# connector.net
KiCad netlist of a schematic drawn in Altium Designer
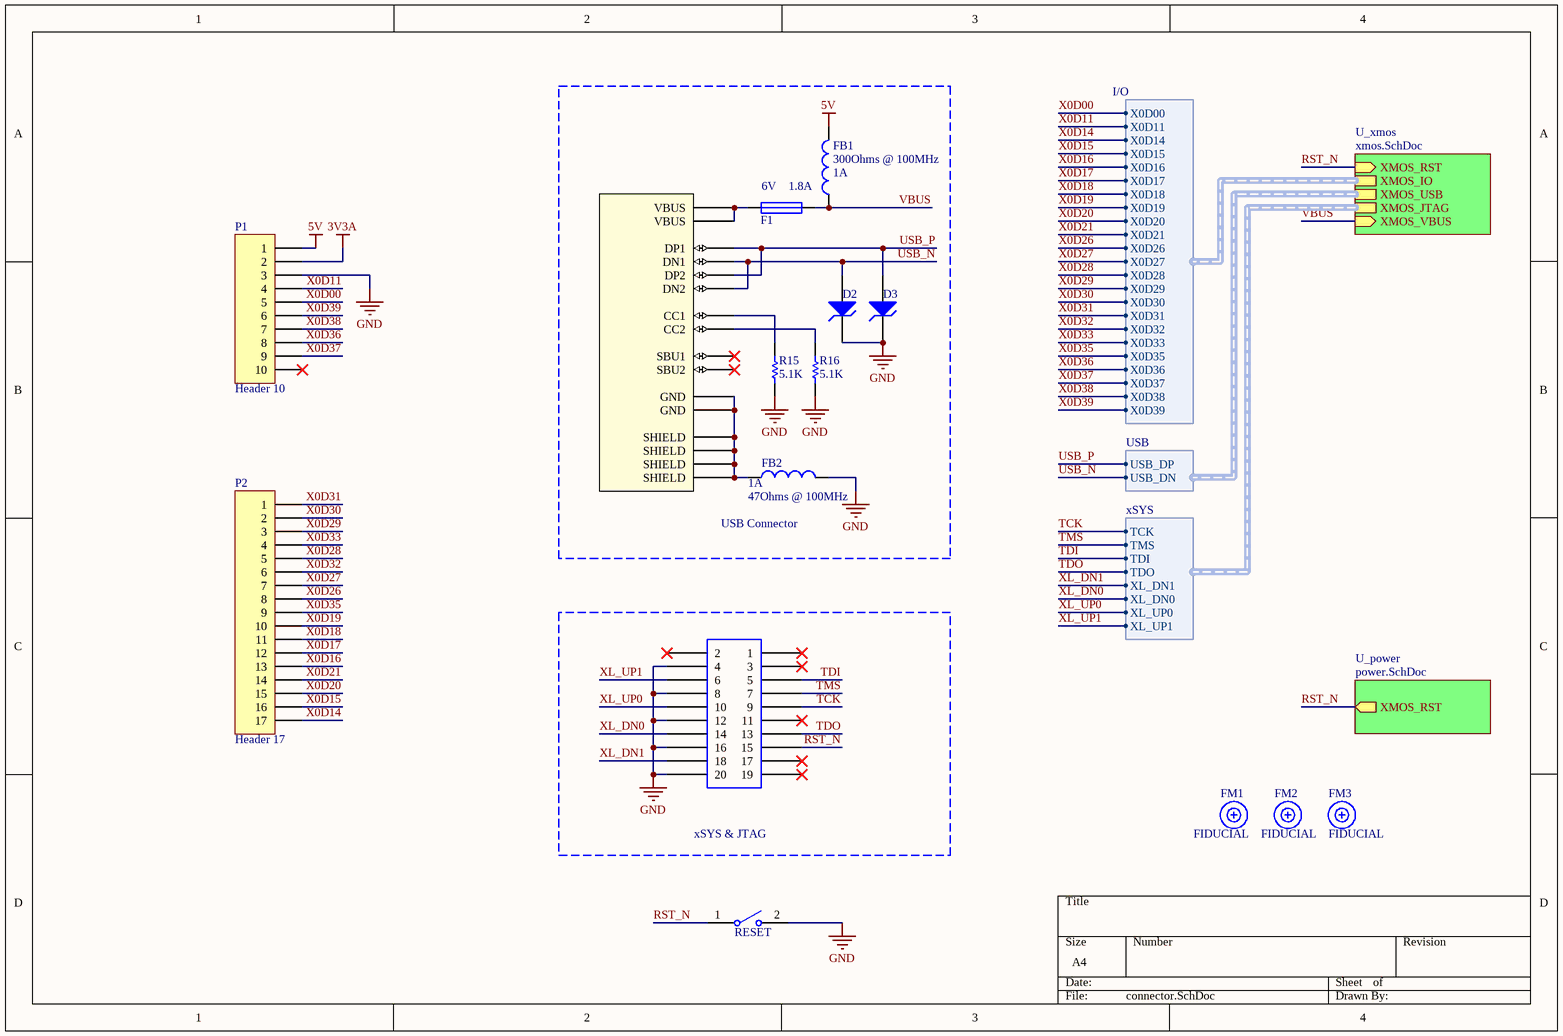
[diagram p0: connector.SchDoc]

(export (version "E")
  (design (tool "Eeschema 10.0.6"))
  (components
    (comp (ref "D2")
      (value "ESD9B")
      (footprint "SOD-923-2")
      (description "ESD Protection Diode")
      (libsource (lib "ON") (part "ESD9B"))
    )
    (comp (ref "D3")
      (value "ESD9B")
      (footprint "SOD-923-2")
      (description "ESD Protection Diode")
      (libsource (lib "ON") (part "ESD9B"))
    )
    (comp (ref "F1")
      (value "Fuse")
      (footprint "0805")
      (description "Fuses")
      (fields (field (name "VOLTAGERATINGDC") "6V") (field (name "CURRENTTRIP") "1.8A"))
      (libsource (lib "Fuses") (part "Fuse"))
    )
    (comp (ref "FB1")
      (value "Ferrite")
      (footprint "IND_1608")
      (description "Ferrite Beads")
      (fields (field (name "IMPEDANCE") "300Ohms @ 100MHz") (field (name "MAXIMUMDCCURRENT") "1A"))
      (libsource (lib "Inductors") (part "Ferrite"))
    )
    (comp (ref "FB2")
      (value "Ferrite")
      (footprint "IND_1608")
      (description "Ferrite Beads")
      (fields (field (name "IMPEDANCE") "47Ohms @ 100MHz") (field (name "MAXIMUMDCCURRENT") "1A"))
      (libsource (lib "Inductors") (part "Ferrite"))
    )
    (comp (ref "FM1")
      (value "FIDUCIAL")
      (footprint "FIDUCIAL_10_20")
      (description "Fiducial, dot")
      (libsource (lib "Fiducial") (part "FIDUCIAL"))
    )
    (comp (ref "FM2")
      (value "FIDUCIAL")
      (footprint "FIDUCIAL_10_20")
      (description "Fiducial, dot")
      (libsource (lib "Fiducial") (part "FIDUCIAL"))
    )
    (comp (ref "FM3")
      (value "FIDUCIAL")
      (footprint "FIDUCIAL_10_20")
      (description "Fiducial, dot")
      (libsource (lib "Fiducial") (part "FIDUCIAL"))
    )
    (comp (ref "J1")
      (value "USB C RECEPTACLE(1)")
      (footprint "USB C RECEPTACLE 2(1)")
      (description "Universal Serial Bus (USB) I/O Receptacle, Type C, 2.0")
      (libsource (lib "Connectors") (part "USB C RECEPTACLE(1)"))
    )
    (comp (ref "J2")
      (value "DC3-20P")
      (footprint "IDC-20 (1)")
      (description "20-Pin Shrouded Header (IDC) Right Angle")
      (libsource (lib "Connectors") (part "DC3-20P"))
    )
    (comp (ref "P1")
      (value "Header 10")
      (footprint "HDR1X10")
      (description "Header, 10-Pin")
      (fields (field (name "PUBLISHER") "Altium Limited"))
      (libsource (lib "Miscellaneous Connectors") (part "Header 10"))
    )
    (comp (ref "P2")
      (value "Header 17")
      (footprint "HDR1X17")
      (description "Header, 17-Pin")
      (fields (field (name "PUBLISHER") "Altium Limited"))
      (libsource (lib "Miscellaneous Connectors") (part "Header 17"))
    )
    (comp (ref "R15")
      (value "5.1K")
      (footprint "RC0603N")
      (description "Chip Resistors")
      (fields (field (name "Comment") "RES"))
      (libsource (lib "Resistors") (part "RES"))
    )
    (comp (ref "R16")
      (value "5.1K")
      (footprint "RC0603N")
      (description "Chip Resistors")
      (fields (field (name "Comment") "RES"))
      (libsource (lib "Resistors") (part "RES"))
    )
    (comp (ref "RESET")
      (value "Tact Switch SPST")
      (footprint "TS_SPST_W4.2XD3.2")
      (description "Switch")
      (libsource (lib "Switches") (part "Tact Switch SPST"))
    )
  )
  (nets
    (net (code "4") (name "/RST_N") (class "Default")
      (node (ref "J2") (pin "15") (pinfunction "15_15") (pintype "passive"))
      (node (ref "RESET") (pin "1") (pinfunction "1_1") (pintype "passive"))
    )
    (net (code "5") (name "/TCK") (class "Default")
      (node (ref "J2") (pin "9") (pinfunction "9_9") (pintype "passive"))
    )
    (net (code "6") (name "/TDI") (class "Default")
      (node (ref "J2") (pin "5") (pinfunction "5_5") (pintype "passive"))
    )
    (net (code "7") (name "/TDO") (class "Default")
      (node (ref "J2") (pin "13") (pinfunction "13_13") (pintype "passive"))
    )
    (net (code "8") (name "/TMS") (class "Default")
      (node (ref "J2") (pin "7") (pinfunction "7_7") (pintype "passive"))
    )
    (net (code "9") (name "/USB_N") (class "Default")
      (node (ref "D2") (pin "1") (pinfunction "1_1") (pintype "passive"))
      (node (ref "J1") (pin "A7") (pinfunction "DN1_A7") (pintype "bidirectional"))
      (node (ref "J1") (pin "B7") (pinfunction "DN2_B7") (pintype "bidirectional"))
    )
    (net (code "10") (name "/USB_P") (class "Default")
      (node (ref "D3") (pin "1") (pinfunction "1_1") (pintype "passive"))
      (node (ref "J1") (pin "A6") (pinfunction "DP1_A6") (pintype "bidirectional"))
      (node (ref "J1") (pin "B6") (pinfunction "DP2_B6") (pintype "bidirectional"))
    )
    (net (code "11") (name "/VBUS") (class "Default")
      (node (ref "F1") (pin "2") (pinfunction "2_2") (pintype "passive"))
      (node (ref "FB1") (pin "1") (pinfunction "1_1") (pintype "passive"))
    )
    (net (code "12") (name "/X0D00") (class "Default")
      (node (ref "P1") (pin "5") (pinfunction "5_5") (pintype "passive"))
    )
    (net (code "13") (name "/X0D11") (class "Default")
      (node (ref "P1") (pin "4") (pinfunction "4_4") (pintype "passive"))
    )
    (net (code "14") (name "/X0D14") (class "Default")
      (node (ref "P2") (pin "17") (pinfunction "17_17") (pintype "passive"))
    )
    (net (code "15") (name "/X0D15") (class "Default")
      (node (ref "P2") (pin "16") (pinfunction "16_16") (pintype "passive"))
    )
    (net (code "16") (name "/X0D16") (class "Default")
      (node (ref "P2") (pin "13") (pinfunction "13_13") (pintype "passive"))
    )
    (net (code "17") (name "/X0D17") (class "Default")
      (node (ref "P2") (pin "12") (pinfunction "12_12") (pintype "passive"))
    )
    (net (code "18") (name "/X0D18") (class "Default")
      (node (ref "P2") (pin "11") (pinfunction "11_11") (pintype "passive"))
    )
    (net (code "19") (name "/X0D19") (class "Default")
      (node (ref "P2") (pin "10") (pinfunction "10_10") (pintype "passive"))
    )
    (net (code "20") (name "/X0D20") (class "Default")
      (node (ref "P2") (pin "15") (pinfunction "15_15") (pintype "passive"))
    )
    (net (code "21") (name "/X0D21") (class "Default")
      (node (ref "P2") (pin "14") (pinfunction "14_14") (pintype "passive"))
    )
    (net (code "22") (name "/X0D26") (class "Default")
      (node (ref "P2") (pin "8") (pinfunction "8_8") (pintype "passive"))
    )
    (net (code "23") (name "/X0D27") (class "Default")
      (node (ref "P2") (pin "7") (pinfunction "7_7") (pintype "passive"))
    )
    (net (code "24") (name "/X0D28") (class "Default")
      (node (ref "P2") (pin "5") (pinfunction "5_5") (pintype "passive"))
    )
    (net (code "25") (name "/X0D29") (class "Default")
      (node (ref "P2") (pin "3") (pinfunction "3_3") (pintype "passive"))
    )
    (net (code "26") (name "/X0D30") (class "Default")
      (node (ref "P2") (pin "2") (pinfunction "2_2") (pintype "passive"))
    )
    (net (code "27") (name "/X0D31") (class "Default")
      (node (ref "P2") (pin "1") (pinfunction "1_1") (pintype "passive"))
    )
    (net (code "28") (name "/X0D32") (class "Default")
      (node (ref "P2") (pin "6") (pinfunction "6_6") (pintype "passive"))
    )
    (net (code "29") (name "/X0D33") (class "Default")
      (node (ref "P2") (pin "4") (pinfunction "4_4") (pintype "passive"))
    )
    (net (code "30") (name "/X0D35") (class "Default")
      (node (ref "P2") (pin "9") (pinfunction "9_9") (pintype "passive"))
    )
    (net (code "31") (name "/X0D36") (class "Default")
      (node (ref "P1") (pin "8") (pinfunction "8_8") (pintype "passive"))
    )
    (net (code "32") (name "/X0D37") (class "Default")
      (node (ref "P1") (pin "9") (pinfunction "9_9") (pintype "passive"))
    )
    (net (code "33") (name "/X0D38") (class "Default")
      (node (ref "P1") (pin "7") (pinfunction "7_7") (pintype "passive"))
    )
    (net (code "34") (name "/X0D39") (class "Default")
      (node (ref "P1") (pin "6") (pinfunction "6_6") (pintype "passive"))
    )
    (net (code "35") (name "/XL_DN0") (class "Default")
      (node (ref "J2") (pin "14") (pinfunction "14_14") (pintype "passive"))
    )
    (net (code "36") (name "/XL_DN1") (class "Default")
      (node (ref "J2") (pin "18") (pinfunction "18_18") (pintype "passive"))
    )
    (net (code "37") (name "/XL_UP0") (class "Default")
      (node (ref "J2") (pin "10") (pinfunction "10_10") (pintype "passive"))
    )
    (net (code "38") (name "/XL_UP1") (class "Default")
      (node (ref "J2") (pin "6") (pinfunction "6_6") (pintype "passive"))
    )
    (net (code "42") (name "3V3A") (class "Default")
      (node (ref "P1") (pin "2") (pinfunction "2_2") (pintype "passive"))
    )
    (net (code "43") (name "5V") (class "Default")
      (node (ref "FB1") (pin "2") (pinfunction "2_2") (pintype "passive"))
      (node (ref "P1") (pin "1") (pinfunction "1_1") (pintype "passive"))
    )
    (net (code "44") (name "GND") (class "Default")
      (node (ref "D2") (pin "2") (pinfunction "2_2") (pintype "passive"))
      (node (ref "D3") (pin "2") (pinfunction "2_2") (pintype "passive"))
      (node (ref "FB2") (pin "2") (pinfunction "2_2") (pintype "passive"))
      (node (ref "J2") (pin "12") (pinfunction "12_12") (pintype "passive"))
      (node (ref "J2") (pin "16") (pinfunction "16_16") (pintype "passive"))
      (node (ref "J2") (pin "20") (pinfunction "20_20") (pintype "passive"))
      (node (ref "J2") (pin "4") (pinfunction "4_4") (pintype "passive"))
      (node (ref "J2") (pin "8") (pinfunction "8_8") (pintype "passive"))
      (node (ref "P1") (pin "3") (pinfunction "3_3") (pintype "passive"))
      (node (ref "R15") (pin "1") (pinfunction "1_1") (pintype "passive"))
      (node (ref "R16") (pin "1") (pinfunction "1_1") (pintype "passive"))
      (node (ref "RESET") (pin "2") (pinfunction "2_2") (pintype "passive"))
    )
    (net (code "45") (name "Net-(F1-Pad1)") (class "Default")
      (node (ref "F1") (pin "1") (pinfunction "1_1") (pintype "passive"))
      (node (ref "J1") (pin "A4/B9") (pinfunction "VBUS_A4/B9") (pintype "power_in"))
      (node (ref "J1") (pin "B4/A9") (pinfunction "VBUS_B4/A9") (pintype "power_in"))
    )
    (net (code "46") (name "Net-(FB2-Pad1)") (class "Default")
      (node (ref "FB2") (pin "1") (pinfunction "1_1") (pintype "passive"))
      (node (ref "J1") (pin "A1/B12") (pinfunction "GND_A1/B12") (pintype "passive"))
      (node (ref "J1") (pin "B1/A12") (pinfunction "GND_B1/A12") (pintype "passive"))
      (node (ref "J1") (pin "SH1") (pinfunction "SHIELD_SH1") (pintype "passive"))
      (node (ref "J1") (pin "SH2") (pinfunction "SHIELD_SH2") (pintype "passive"))
      (node (ref "J1") (pin "SH3") (pinfunction "SHIELD_SH3") (pintype "passive"))
      (node (ref "J1") (pin "SH4") (pinfunction "SHIELD_SH4") (pintype "passive"))
    )
    (net (code "47") (name "Net-(J1-CC1)") (class "Default")
      (node (ref "J1") (pin "A5") (pinfunction "CC1_A5") (pintype "bidirectional"))
      (node (ref "R15") (pin "2") (pinfunction "2_2") (pintype "passive"))
    )
    (net (code "48") (name "Net-(J1-CC2)") (class "Default")
      (node (ref "J1") (pin "B5") (pinfunction "CC2_B5") (pintype "bidirectional"))
      (node (ref "R16") (pin "2") (pinfunction "2_2") (pintype "passive"))
    )
    (net (code "49") (name "unconnected-(J1-SBU1-PadA8)") (class "Default")
      (node (ref "J1") (pin "A8") (pinfunction "SBU1_A8") (pintype "bidirectional+no_connect"))
    )
    (net (code "50") (name "unconnected-(J1-SBU2-PadB8)") (class "Default")
      (node (ref "J1") (pin "B8") (pinfunction "SBU2_B8") (pintype "bidirectional+no_connect"))
    )
    (net (code "51") (name "unconnected-(J2-Pad1)") (class "Default")
      (node (ref "J2") (pin "1") (pinfunction "1_1") (pintype "passive+no_connect"))
    )
    (net (code "52") (name "unconnected-(J2-Pad2)") (class "Default")
      (node (ref "J2") (pin "2") (pinfunction "2_2") (pintype "passive+no_connect"))
    )
    (net (code "53") (name "unconnected-(J2-Pad3)") (class "Default")
      (node (ref "J2") (pin "3") (pinfunction "3_3") (pintype "passive+no_connect"))
    )
    (net (code "54") (name "unconnected-(J2-Pad11)") (class "Default")
      (node (ref "J2") (pin "11") (pinfunction "11_11") (pintype "passive+no_connect"))
    )
    (net (code "55") (name "unconnected-(J2-Pad17)") (class "Default")
      (node (ref "J2") (pin "17") (pinfunction "17_17") (pintype "passive+no_connect"))
    )
    (net (code "56") (name "unconnected-(J2-Pad19)") (class "Default")
      (node (ref "J2") (pin "19") (pinfunction "19_19") (pintype "passive+no_connect"))
    )
    (net (code "57") (name "unconnected-(P1-Pad10)") (class "Default")
      (node (ref "P1") (pin "10") (pinfunction "10_10") (pintype "passive+no_connect"))
    )
  )
)
